# avr-isp-adapter.net
KiCad netlist of a schematic drawn in EAGLE
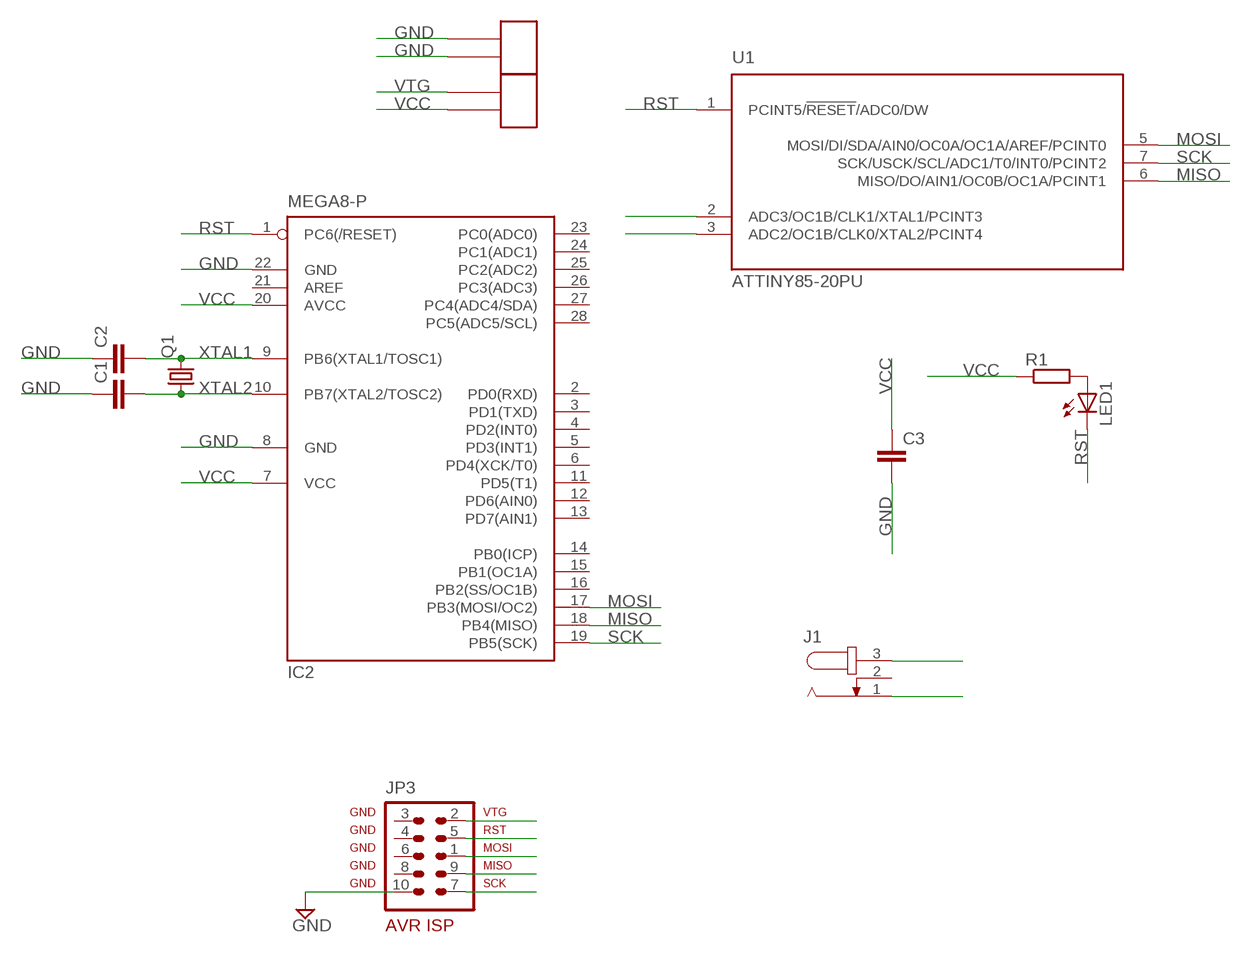
[diagram p0: schematic, sheet 1]

(export (version "E")
  (design (tool "Eeschema 10.0.6"))
  (components
    (comp (ref "C1")
      (value "C-EUC0805")
      (footprint "eagle-import:C0805")
      (libsource (lib "eagle-import") (part "C-EUC0805"))
    )
    (comp (ref "C2")
      (value "C-EUC0805")
      (footprint "eagle-import:C0805")
      (libsource (lib "eagle-import") (part "C-EUC0805"))
    )
    (comp (ref "C3")
      (value "C-EUC0805")
      (footprint "eagle-import:C0805")
      (libsource (lib "eagle-import") (part "C-EUC0805"))
    )
    (comp (ref "IC2")
      (value "MEGA8-P")
      (footprint "eagle-import:DIL28-3")
      (libsource (lib "eagle-import") (part "MEGA8-P"))
    )
    (comp (ref "J1")
      (value "JACK-PLUG1")
      (footprint "eagle-import:SPC4078")
      (libsource (lib "eagle-import") (part "JACK-PLUG1"))
    )
    (comp (ref "JP3")
      (value "AVR-ISP-10")
      (footprint "eagle-import:AVR-ISP-10")
      (libsource (lib "eagle-import") (part "AVR-ISP-10"))
    )
    (comp (ref "LED1")
      (value "LED3MM")
      (footprint "eagle-import:LED3MM")
      (libsource (lib "eagle-import") (part "LED3MM"))
    )
    (comp (ref "Q1")
      (value "CRYSTALHC49S")
      (footprint "eagle-import:HC49_S")
      (libsource (lib "eagle-import") (part "CRYSTALHC49S"))
    )
    (comp (ref "R1")
      (value "R-EU_M0805")
      (footprint "eagle-import:M0805")
      (libsource (lib "eagle-import") (part "R-EU_M0805"))
    )
    (comp (ref "U$1")
      (value "MA02-1")
      (footprint "eagle-import:MA02-1")
      (libsource (lib "eagle-import") (part "MA02-1"))
    )
    (comp (ref "U$2")
      (value "MA02-1")
      (footprint "eagle-import:MA02-1")
      (libsource (lib "eagle-import") (part "MA02-1"))
    )
    (comp (ref "U1")
      (value "ATTINY85-20PU")
      (footprint "eagle-import:DIP-8")
      (fields (field (name "MANUFACTURER") "Atmel"))
      (libsource (lib "eagle-import") (part "ATTINY5-?20PU8"))
    )
  )
  (nets
    (net (code "1") (name "/MISO") (class "Default")
      (node (ref "IC2") (pin "18") (pinfunction "PB4(MISO)_18") (pintype "bidirectional"))
      (node (ref "JP3") (pin "9") (pinfunction "9_9") (pintype "passive"))
      (node (ref "U1") (pin "6") (pinfunction "MISO/DO/AIN1/OC0B/OC1A/PCINT1_6") (pintype "bidirectional"))
    )
    (net (code "2") (name "/MOSI") (class "Default")
      (node (ref "IC2") (pin "17") (pinfunction "PB3(MOSI/OC2)_17") (pintype "bidirectional"))
      (node (ref "JP3") (pin "1") (pinfunction "1_1") (pintype "passive"))
      (node (ref "U1") (pin "5") (pinfunction "MOSI/DI/SDA/AIN0/OC0A/OC1A/AREF/PCINT0_5") (pintype "bidirectional"))
    )
    (net (code "3") (name "/RST") (class "Default")
      (node (ref "IC2") (pin "1") (pinfunction "PC6(/RESET)_1") (pintype "bidirectional"))
      (node (ref "JP3") (pin "5") (pinfunction "5_5") (pintype "passive"))
      (node (ref "LED1") (pin "K") (pinfunction "C_K") (pintype "passive"))
      (node (ref "U1") (pin "1") (pinfunction "PCINT5/~{RESET}/ADC0/DW_1") (pintype "bidirectional"))
    )
    (net (code "4") (name "/SCK") (class "Default")
      (node (ref "IC2") (pin "19") (pinfunction "PB5(SCK)_19") (pintype "bidirectional"))
      (node (ref "JP3") (pin "7") (pinfunction "7_7") (pintype "passive"))
      (node (ref "U1") (pin "7") (pinfunction "SCK/USCK/SCL/ADC1/T0/INT0/PCINT2_7") (pintype "bidirectional"))
    )
    (net (code "5") (name "/VCC") (class "Default")
      (node (ref "C3") (pin "1") (pinfunction "1_1") (pintype "passive"))
      (node (ref "IC2") (pin "20") (pinfunction "AVCC_20") (pintype "power_in"))
      (node (ref "IC2") (pin "7") (pinfunction "VCC_7") (pintype "power_in"))
      (node (ref "J1") (pin "3") (pinfunction "3_3") (pintype "passive"))
      (node (ref "R1") (pin "1") (pinfunction "1_1") (pintype "passive"))
      (node (ref "U$1") (pin "P2") (pinfunction "P2_P2") (pintype "bidirectional"))
    )
    (net (code "6") (name "/VTG") (class "Default")
      (node (ref "JP3") (pin "2") (pinfunction "2_2") (pintype "passive"))
      (node (ref "U$1") (pin "P1") (pinfunction "P1_P1") (pintype "bidirectional"))
    )
    (net (code "7") (name "/XTAL1") (class "Default")
      (node (ref "C2") (pin "2") (pinfunction "2_2") (pintype "passive"))
      (node (ref "IC2") (pin "9") (pinfunction "PB6(XTAL1/TOSC1)_9") (pintype "bidirectional"))
      (node (ref "Q1") (pin "2") (pinfunction "2_2") (pintype "passive"))
      (node (ref "U1") (pin "2") (pinfunction "ADC3/OC1B/CLK1/XTAL1/PCINT3_2") (pintype "bidirectional"))
    )
    (net (code "8") (name "/XTAL2") (class "Default")
      (node (ref "C1") (pin "2") (pinfunction "2_2") (pintype "passive"))
      (node (ref "IC2") (pin "10") (pinfunction "PB7(XTAL2/TOSC2)_10") (pintype "bidirectional"))
      (node (ref "Q1") (pin "1") (pinfunction "1_1") (pintype "passive"))
      (node (ref "U1") (pin "3") (pinfunction "ADC2/OC1B/CLK0/XTAL2/PCINT4_3") (pintype "bidirectional"))
    )
    (net (code "9") (name "GND") (class "Default")
      (node (ref "C1") (pin "1") (pinfunction "1_1") (pintype "passive"))
      (node (ref "C2") (pin "1") (pinfunction "1_1") (pintype "passive"))
      (node (ref "C3") (pin "2") (pinfunction "2_2") (pintype "passive"))
      (node (ref "IC2") (pin "22") (pinfunction "GND_22") (pintype "power_in"))
      (node (ref "IC2") (pin "8") (pinfunction "GND_8") (pintype "power_in"))
      (node (ref "J1") (pin "1") (pinfunction "1_1") (pintype "passive"))
      (node (ref "JP3") (pin "10") (pinfunction "10_10") (pintype "passive"))
      (node (ref "U$2") (pin "P1") (pinfunction "P1_P1") (pintype "bidirectional"))
      (node (ref "U$2") (pin "P2") (pinfunction "P2_P2") (pintype "bidirectional"))
    )
    (net (code "10") (name "Net-(LED1-PadA)") (class "Default")
      (node (ref "LED1") (pin "A") (pinfunction "A_A") (pintype "passive"))
      (node (ref "R1") (pin "2") (pinfunction "2_2") (pintype "passive"))
    )
    (net (code "11") (name "unconnected-(IC2-AREF-Pad21)") (class "Default")
      (node (ref "IC2") (pin "21") (pinfunction "AREF_21") (pintype "passive"))
    )
    (net (code "12") (name "unconnected-(IC2-PB0(ICP)-Pad14)") (class "Default")
      (node (ref "IC2") (pin "14") (pinfunction "PB0(ICP)_14") (pintype "bidirectional"))
    )
    (net (code "13") (name "unconnected-(IC2-PB1(OC1A)-Pad15)") (class "Default")
      (node (ref "IC2") (pin "15") (pinfunction "PB1(OC1A)_15") (pintype "bidirectional"))
    )
    (net (code "14") (name "unconnected-(IC2-PB2(SS{slash}OC1B)-Pad16)") (class "Default")
      (node (ref "IC2") (pin "16") (pinfunction "PB2(SS/OC1B)_16") (pintype "bidirectional"))
    )
    (net (code "15") (name "unconnected-(IC2-PC0(ADC0)-Pad23)") (class "Default")
      (node (ref "IC2") (pin "23") (pinfunction "PC0(ADC0)_23") (pintype "bidirectional"))
    )
    (net (code "16") (name "unconnected-(IC2-PC1(ADC1)-Pad24)") (class "Default")
      (node (ref "IC2") (pin "24") (pinfunction "PC1(ADC1)_24") (pintype "bidirectional"))
    )
    (net (code "17") (name "unconnected-(IC2-PC2(ADC2)-Pad25)") (class "Default")
      (node (ref "IC2") (pin "25") (pinfunction "PC2(ADC2)_25") (pintype "bidirectional"))
    )
    (net (code "18") (name "unconnected-(IC2-PC3(ADC3)-Pad26)") (class "Default")
      (node (ref "IC2") (pin "26") (pinfunction "PC3(ADC3)_26") (pintype "bidirectional"))
    )
    (net (code "19") (name "unconnected-(IC2-PC4(ADC4{slash}SDA)-Pad27)") (class "Default")
      (node (ref "IC2") (pin "27") (pinfunction "PC4(ADC4/SDA)_27") (pintype "bidirectional"))
    )
    (net (code "20") (name "unconnected-(IC2-PC5(ADC5{slash}SCL)-Pad28)") (class "Default")
      (node (ref "IC2") (pin "28") (pinfunction "PC5(ADC5/SCL)_28") (pintype "bidirectional"))
    )
    (net (code "21") (name "unconnected-(IC2-PD0(RXD)-Pad2)") (class "Default")
      (node (ref "IC2") (pin "2") (pinfunction "PD0(RXD)_2") (pintype "bidirectional"))
    )
    (net (code "22") (name "unconnected-(IC2-PD1(TXD)-Pad3)") (class "Default")
      (node (ref "IC2") (pin "3") (pinfunction "PD1(TXD)_3") (pintype "bidirectional"))
    )
    (net (code "23") (name "unconnected-(IC2-PD2(INT0)-Pad4)") (class "Default")
      (node (ref "IC2") (pin "4") (pinfunction "PD2(INT0)_4") (pintype "bidirectional"))
    )
    (net (code "24") (name "unconnected-(IC2-PD3(INT1)-Pad5)") (class "Default")
      (node (ref "IC2") (pin "5") (pinfunction "PD3(INT1)_5") (pintype "bidirectional"))
    )
    (net (code "25") (name "unconnected-(IC2-PD4(XCK{slash}T0)-Pad6)") (class "Default")
      (node (ref "IC2") (pin "6") (pinfunction "PD4(XCK/T0)_6") (pintype "bidirectional"))
    )
    (net (code "26") (name "unconnected-(IC2-PD5(T1)-Pad11)") (class "Default")
      (node (ref "IC2") (pin "11") (pinfunction "PD5(T1)_11") (pintype "bidirectional"))
    )
    (net (code "27") (name "unconnected-(IC2-PD6(AIN0)-Pad12)") (class "Default")
      (node (ref "IC2") (pin "12") (pinfunction "PD6(AIN0)_12") (pintype "bidirectional"))
    )
    (net (code "28") (name "unconnected-(IC2-PD7(AIN1)-Pad13)") (class "Default")
      (node (ref "IC2") (pin "13") (pinfunction "PD7(AIN1)_13") (pintype "bidirectional"))
    )
    (net (code "29") (name "unconnected-(J1-Pad2)") (class "Default")
      (node (ref "J1") (pin "2") (pinfunction "2_2") (pintype "passive"))
    )
    (net (code "30") (name "unconnected-(JP3-Pad3)") (class "Default")
      (node (ref "JP3") (pin "3") (pinfunction "3_3") (pintype "passive"))
    )
    (net (code "31") (name "unconnected-(JP3-Pad4)") (class "Default")
      (node (ref "JP3") (pin "4") (pinfunction "4_4") (pintype "passive"))
    )
    (net (code "32") (name "unconnected-(JP3-Pad6)") (class "Default")
      (node (ref "JP3") (pin "6") (pinfunction "6_6") (pintype "passive"))
    )
    (net (code "33") (name "unconnected-(JP3-Pad8)") (class "Default")
      (node (ref "JP3") (pin "8") (pinfunction "8_8") (pintype "passive"))
    )
  )
)
